# SPDIF.net
KiCad netlist of a schematic drawn in Altium Designer
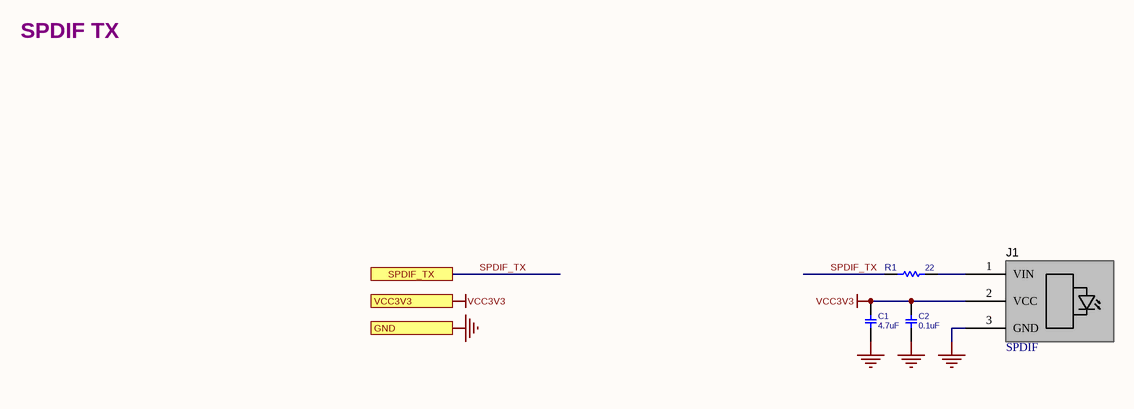
[diagram p0: SPDIF.SchDoc]

(export (version "E")
  (design (tool "Eeschema 10.0.6"))
  (components
    (comp (ref "C1")
      (value "4.7uF")
      (footprint "C0402")
      (description "CAP, MLCC")
      (fields (field (name "MANF_P#") "CL05A475MP5NRNC") (field (name "MANF") "Samsung"))
      (libsource (lib "passive_smd") (part "CAP_SMD_MLCC"))
    )
    (comp (ref "C2")
      (value "0.1uF")
      (footprint "C0402")
      (description "CAP, MLCC")
      (fields (field (name "MANF_P#") "GRM155R61E104") (field (name "MANF") "Murata"))
      (libsource (lib "passive_smd") (part "CAP_SMD_MLCC"))
    )
    (comp (ref "J1")
      (value "SPDIF")
      (footprint "SPDIF_T")
      (description "FIBER OPTIC TRANSMITTER IR, 25Mbps")
      (fields (field (name "MANF") "Everlight") (field (name "MANF_P#") "PLT237/T10WH"))
      (libsource (lib "conn_jackAV") (part "SPDIF_T_PLT237"))
    )
    (comp (ref "R1")
      (value "22")
      (footprint "R0402")
      (description "RESISTOR, SMD")
      (libsource (lib "passive_res_smd") (part "RES_SMD"))
    )
  )
  (nets
    (net (code "1") (name "/SPDIF_TX") (class "Default")
      (node (ref "R1") (pin "2") (pinfunction "2_2") (pintype "passive"))
    )
    (net (code "2") (name "GND") (class "Default")
      (node (ref "C1") (pin "1") (pinfunction "1_1") (pintype "passive"))
      (node (ref "C2") (pin "1") (pinfunction "1_1") (pintype "passive"))
      (node (ref "J1") (pin "3") (pinfunction "GND_3") (pintype "passive"))
    )
    (net (code "3") (name "Net-(J1-VIN)") (class "Default")
      (node (ref "J1") (pin "1") (pinfunction "VIN_1") (pintype "passive"))
      (node (ref "R1") (pin "1") (pinfunction "1_1") (pintype "passive"))
    )
    (net (code "4") (name "VCC3V3") (class "Default")
      (node (ref "C1") (pin "2") (pinfunction "2_2") (pintype "passive"))
      (node (ref "C2") (pin "2") (pinfunction "2_2") (pintype "passive"))
      (node (ref "J1") (pin "2") (pinfunction "VCC_2") (pintype "passive"))
    )
  )
)
